# SBH_BMS.net
KiCad netlist of a schematic drawn in Altium Designer
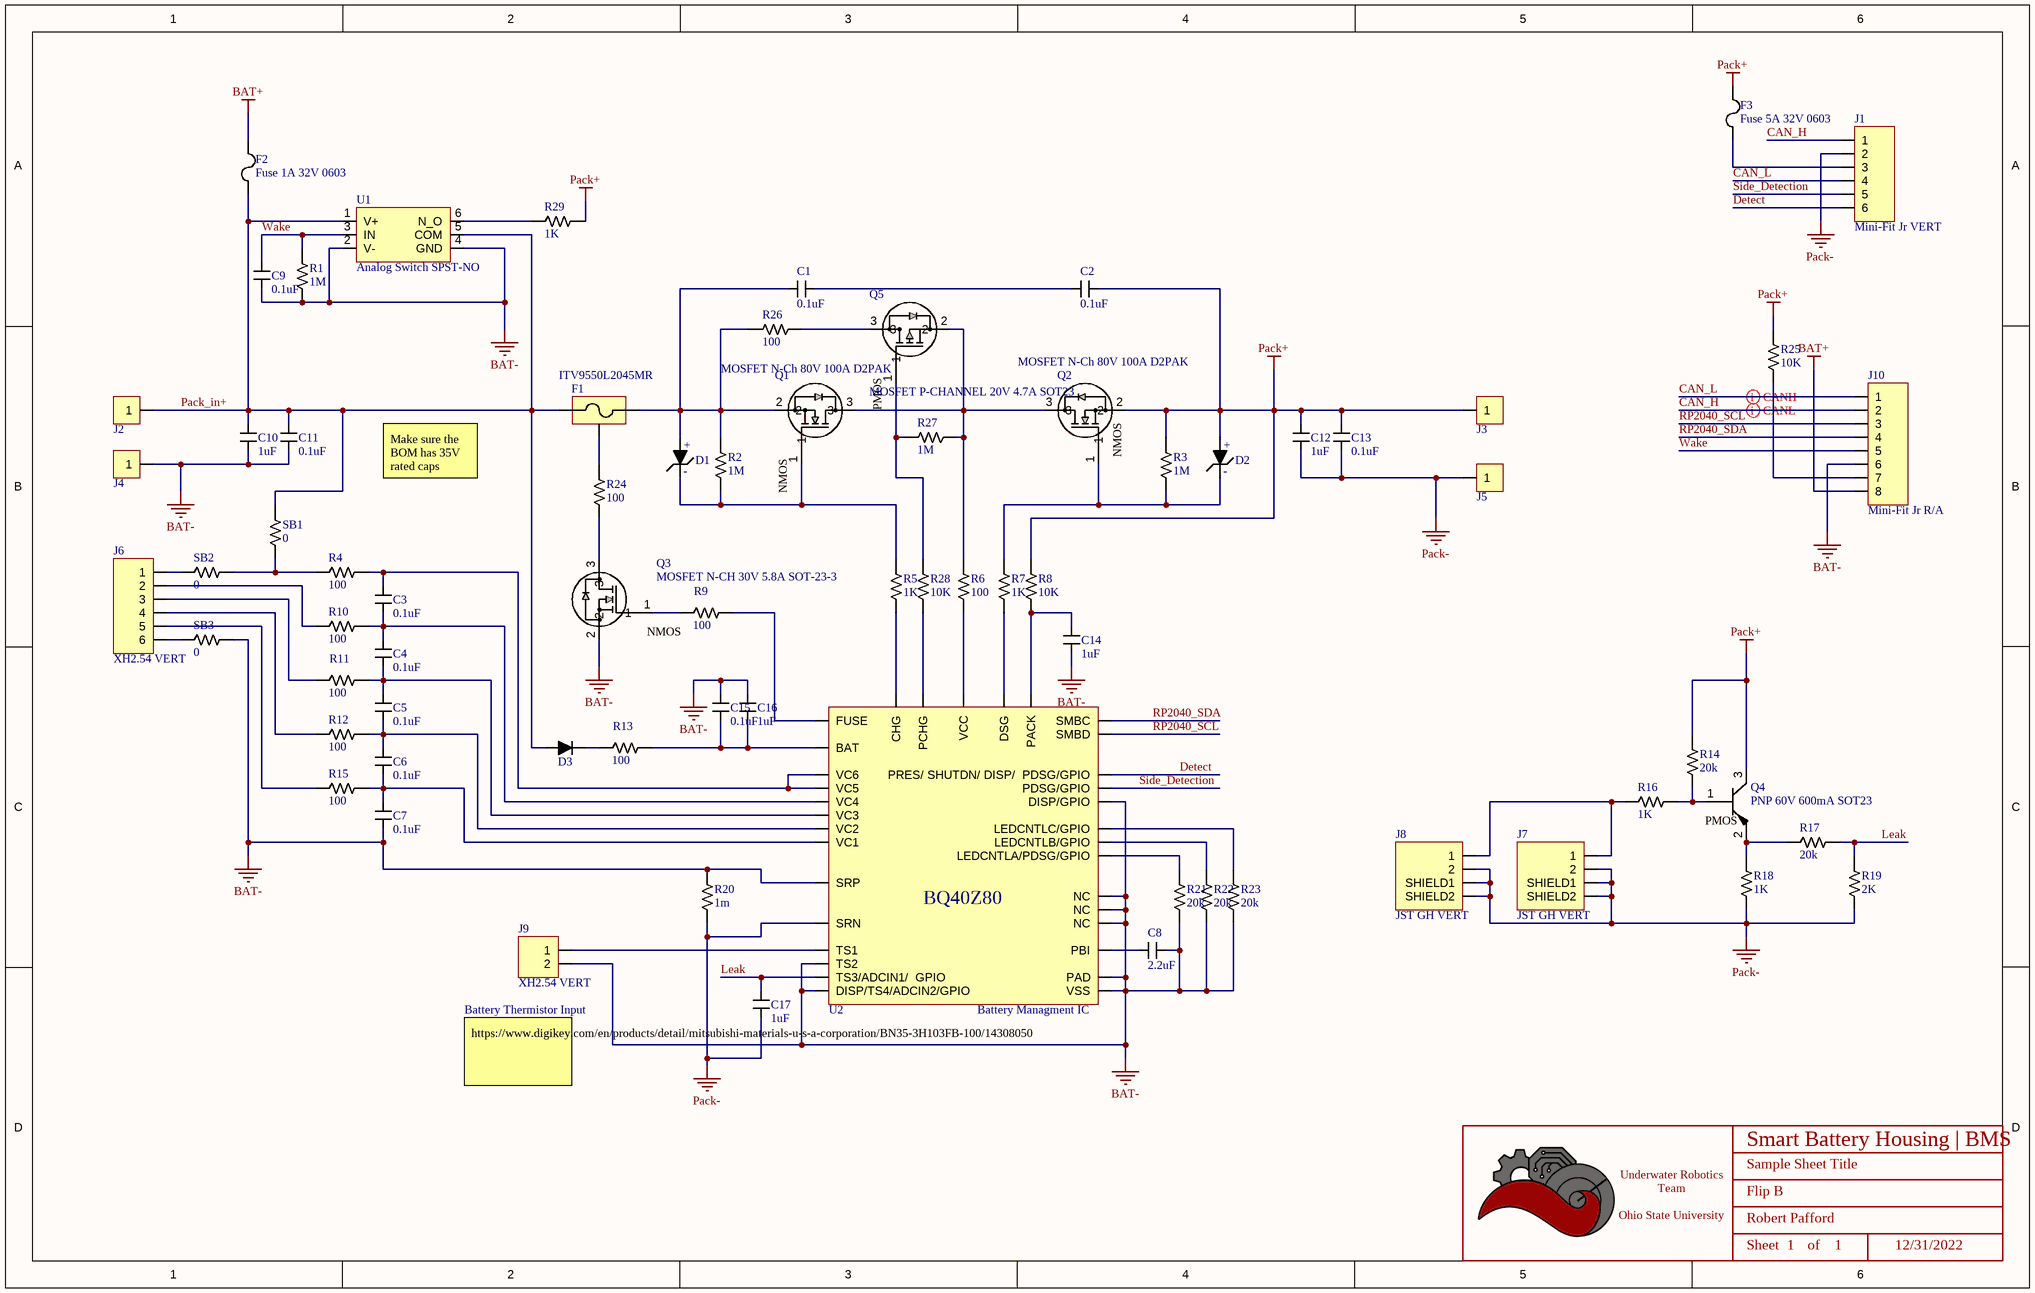
[diagram p0: SBH_BMS.SchDoc]

(export (version "E")
  (design (tool "Eeschema 10.0.6"))
  (components
    (comp (ref "*")
      (value "Title_Block")
      (footprint "LOGO")
      (description "UWRT Schematic Title Block Template\r\n\r\nCreated June 2021, Dylan Trainor")
      (libsource (lib "UWRT") (part "Title_Block"))
    )
    (comp (ref "C1")
      (value "0.1uF")
      (footprint "CAPACITOR_0402")
      (description "Cap 100nF 25V +/-10%\r\nCeramic 0402")
      (fields
        (field (name "TOLERANCE") "+/- 10%")
        (field (name "VOLTAGE") "25V")
        (field (name "MADE BY") "Robert Pafford")
      )
      (libsource (lib "Capacitors") (part "CAPACITOR_0.1uF_0402"))
    )
    (comp (ref "C2")
      (value "0.1uF")
      (footprint "CAPACITOR_0402")
      (description "Cap 100nF 25V +/-10%\r\nCeramic 0402")
      (fields
        (field (name "TOLERANCE") "+/- 10%")
        (field (name "VOLTAGE") "25V")
        (field (name "MADE BY") "Robert Pafford")
      )
      (libsource (lib "Capacitors") (part "CAPACITOR_0.1uF_0402"))
    )
    (comp (ref "C3")
      (value "0.1uF")
      (footprint "CAPACITOR_0402")
      (description "Cap 100nF 25V +/-10%\r\nCeramic 0402")
      (fields
        (field (name "TOLERANCE") "+/- 10%")
        (field (name "VOLTAGE") "25V")
        (field (name "MADE BY") "Robert Pafford")
      )
      (libsource (lib "Capacitors") (part "CAPACITOR_0.1uF_0402"))
    )
    (comp (ref "C4")
      (value "0.1uF")
      (footprint "CAPACITOR_0402")
      (description "Cap 100nF 25V +/-10%\r\nCeramic 0402")
      (fields
        (field (name "TOLERANCE") "+/- 10%")
        (field (name "VOLTAGE") "25V")
        (field (name "MADE BY") "Robert Pafford")
      )
      (libsource (lib "Capacitors") (part "CAPACITOR_0.1uF_0402"))
    )
    (comp (ref "C5")
      (value "0.1uF")
      (footprint "CAPACITOR_0402")
      (description "Cap 100nF 25V +/-10%\r\nCeramic 0402")
      (fields
        (field (name "TOLERANCE") "+/- 10%")
        (field (name "VOLTAGE") "25V")
        (field (name "MADE BY") "Robert Pafford")
      )
      (libsource (lib "Capacitors") (part "CAPACITOR_0.1uF_0402"))
    )
    (comp (ref "C6")
      (value "0.1uF")
      (footprint "CAPACITOR_0402")
      (description "Cap 100nF 25V +/-10%\r\nCeramic 0402")
      (fields
        (field (name "TOLERANCE") "+/- 10%")
        (field (name "VOLTAGE") "25V")
        (field (name "MADE BY") "Robert Pafford")
      )
      (libsource (lib "Capacitors") (part "CAPACITOR_0.1uF_0402"))
    )
    (comp (ref "C7")
      (value "0.1uF")
      (footprint "CAPACITOR_0402")
      (description "Cap 100nF 25V +/-10%\r\nCeramic 0402")
      (fields
        (field (name "TOLERANCE") "+/- 10%")
        (field (name "VOLTAGE") "25V")
        (field (name "MADE BY") "Robert Pafford")
      )
      (libsource (lib "Capacitors") (part "CAPACITOR_0.1uF_0402"))
    )
    (comp (ref "C8")
      (value "2.2uF")
      (footprint "CAPACITOR_0402")
      (description "Cap 2.2uF 35V +/-10%\r\nCeramic 0402")
      (fields
        (field (name "TOLERANCE") "+/- 10%")
        (field (name "VOLTAGE") "35V")
        (field (name "MADE BY") "Flip B")
      )
      (libsource (lib "Capacitors") (part "CAPACITOR_2.2uF_0402"))
    )
    (comp (ref "C9")
      (value "0.1uF")
      (footprint "CAPACITOR_0402")
      (description "Cap 100nF 25V +/-10%\r\nCeramic 0402")
      (fields
        (field (name "TOLERANCE") "+/- 10%")
        (field (name "VOLTAGE") "25V")
        (field (name "MADE BY") "Robert Pafford")
      )
      (libsource (lib "Capacitors") (part "CAPACITOR_0.1uF_0402"))
    )
    (comp (ref "C10")
      (value "1uF")
      (footprint "CAPACITOR_0402")
      (description "Cap 1uF 16V +/-10%\r\nCeramic 0402")
      (fields
        (field (name "TOLERANCE") "+/- 10%")
        (field (name "VOLTAGE") "16V")
        (field (name "MADE BY") "Robert Pafford")
      )
      (libsource (lib "Capacitors") (part "CAPACITOR_1uF_0402"))
    )
    (comp (ref "C11")
      (value "0.1uF")
      (footprint "CAPACITOR_0402")
      (description "Cap 100nF 25V +/-10%\r\nCeramic 0402")
      (fields
        (field (name "TOLERANCE") "+/- 10%")
        (field (name "VOLTAGE") "25V")
        (field (name "MADE BY") "Robert Pafford")
      )
      (libsource (lib "Capacitors") (part "CAPACITOR_0.1uF_0402"))
    )
    (comp (ref "C12")
      (value "1uF")
      (footprint "CAPACITOR_0402")
      (description "Cap 1uF 16V +/-10%\r\nCeramic 0402")
      (fields
        (field (name "TOLERANCE") "+/- 10%")
        (field (name "VOLTAGE") "16V")
        (field (name "MADE BY") "Robert Pafford")
      )
      (libsource (lib "Capacitors") (part "CAPACITOR_1uF_0402"))
    )
    (comp (ref "C13")
      (value "0.1uF")
      (footprint "CAPACITOR_0402")
      (description "Cap 100nF 25V +/-10%\r\nCeramic 0402")
      (fields
        (field (name "TOLERANCE") "+/- 10%")
        (field (name "VOLTAGE") "25V")
        (field (name "MADE BY") "Robert Pafford")
      )
      (libsource (lib "Capacitors") (part "CAPACITOR_0.1uF_0402"))
    )
    (comp (ref "C14")
      (value "1uF")
      (footprint "CAPACITOR_0402")
      (description "Cap 1uF 16V +/-10%\r\nCeramic 0402")
      (fields
        (field (name "TOLERANCE") "+/- 10%")
        (field (name "VOLTAGE") "16V")
        (field (name "MADE BY") "Robert Pafford")
      )
      (libsource (lib "Capacitors") (part "CAPACITOR_1uF_0402"))
    )
    (comp (ref "C15")
      (value "0.1uF")
      (footprint "CAPACITOR_0402")
      (description "Cap 100nF 25V +/-10%\r\nCeramic 0402")
      (fields
        (field (name "TOLERANCE") "+/- 10%")
        (field (name "VOLTAGE") "25V")
        (field (name "MADE BY") "Robert Pafford")
      )
      (libsource (lib "Capacitors") (part "CAPACITOR_0.1uF_0402"))
    )
    (comp (ref "C16")
      (value "1uF")
      (footprint "CAPACITOR_0402")
      (description "Cap 1uF 16V +/-10%\r\nCeramic 0402")
      (fields
        (field (name "TOLERANCE") "+/- 10%")
        (field (name "VOLTAGE") "16V")
        (field (name "MADE BY") "Robert Pafford")
      )
      (libsource (lib "Capacitors") (part "CAPACITOR_1uF_0402"))
    )
    (comp (ref "C17")
      (value "1uF")
      (footprint "CAPACITOR_0402")
      (description "Cap 1uF 16V +/-10%\r\nCeramic 0402")
      (fields
        (field (name "TOLERANCE") "+/- 10%")
        (field (name "VOLTAGE") "16V")
        (field (name "MADE BY") "Robert Pafford")
      )
      (libsource (lib "Capacitors") (part "CAPACITOR_1uF_0402"))
    )
    (comp (ref "D1")
      (value "Zener_Diode_16V_500mW")
      (footprint "SOD-123")
      (description "Zener Diode ¦ 16 V ¦ 500 mW ¦ SOD-123")
      (fields (field (name "POWER") "500mW") (field (name "MADE BY") "Flip B"))
      (libsource (lib "Diodes") (part "Zener_Diode_16V_500mW"))
    )
    (comp (ref "D2")
      (value "Zener_Diode_16V_500mW")
      (footprint "SOD-123")
      (description "Zener Diode ¦ 16 V ¦ 500 mW ¦ SOD-123")
      (fields (field (name "POWER") "500mW") (field (name "MADE BY") "Flip B"))
      (libsource (lib "Diodes") (part "Zener_Diode_16V_500mW"))
    )
    (comp (ref "D3")
      (value "MBR0520LT3G")
      (footprint "SOD-123")
      (description "Schottky Diode, 20V reverse breakdown, 500mA, Vf = 0.385V")
      (fields (field (name "MADE BY") "Flip B"))
      (libsource (lib "Diodes") (part "SCHOTTKY_20V_500mA"))
    )
    (comp (ref "F1")
      (value "ITV9550L2045MR")
      (footprint "ITV9550")
      (description "LittelFuse  ¦ 45A ¦ 5S ¦ SMD ¦ Self-Control Protector")
      (fields (field (name "CREATED BY") "Flip B"))
      (libsource (lib "Fuses") (part "ITV9550L2045MR"))
    )
    (comp (ref "F2")
      (value "Fuse 1A 32V 0603")
      (footprint "2-SMD Fuse 0603")
      (description "Pansonic ¦ 32V ¦ 1A ¦ 0603 ¦ Fast Blow")
      (fields
        (field (name "MANUFACTURER_PART_NUMBER") "ERB-RE1R00V")
        (field (name "CREATED BY") "Nathan Ayer")
      )
      (libsource (lib "Fuses") (part "ERB-RE1R00V"))
    )
    (comp (ref "F3")
      (value "Fuse 5A 32V 0603")
      (footprint "2-SMD Fuse 0603")
      (description "Pansonic ¦ 32V ¦ 5A ¦ 0603 ¦ Fast Blow")
      (fields
        (field (name "MANUFACTURER_PART_NUMBER") "ERB-RE5R00V")
        (field (name "CREATED BY") "Robert Pafford")
      )
      (libsource (lib "Fuses") (part "ERB-RE5R00V"))
    )
    (comp (ref "J1")
      (value "Mini-Fit Jr VERT")
      (footprint "CONN_MOLEX_MINIFIT JR_6 POS_VERT")
      (description "Molex Minifit Jr. 5566 \r\n6 Pos VERT Natural")
      (fields (field (name "MANUFACTURER") "Molex") (field (name "CREATED BY") "Flip B"))
      (libsource (lib "Connectors") (part "CONN_MOLEX_MINIFIT JR_6POS_VERT"))
    )
    (comp (ref "J2")
      (value "Redcube M4 Term 85A")
      (footprint "Redcube M4 Term 85A")
      (fields (field (name "CREATED BY") "Nahtan Ayer"))
      (libsource (lib "") (part "Redcube M4 Term 85A_1"))
    )
    (comp (ref "J3")
      (value "Redcube M4 Term 85A")
      (footprint "Redcube M4 Term 85A")
      (fields (field (name "CREATED BY") "Nahtan Ayer"))
      (libsource (lib "Connectors") (part "Redcube M4 Term 85A"))
    )
    (comp (ref "J4")
      (value "Redcube M4 Term 85A")
      (footprint "Redcube M4 Term 85A")
      (fields (field (name "CREATED BY") "Nahtan Ayer"))
      (libsource (lib "") (part "Redcube M4 Term 85A_1"))
    )
    (comp (ref "J5")
      (value "Redcube M4 Term 85A")
      (footprint "Redcube M4 Term 85A")
      (fields (field (name "CREATED BY") "Nahtan Ayer"))
      (libsource (lib "Connectors") (part "Redcube M4 Term 85A"))
    )
    (comp (ref "J6")
      (value "XH2.54 VERT")
      (footprint "CONN_JST_XH254_6POS_VERT")
      (description "JST XH 2.54mm Pitch 6 Pos Vertical")
      (fields (field (name "MANUFACTURER") "JST") (field (name "CREATED BY") "Flip B"))
      (libsource (lib "Connectors") (part "CONN_JST_XH254_6POS_VERT"))
    )
    (comp (ref "J7")
      (value "JST GH VERT")
      (footprint "CONN_JST_SM02B-GHS-TB(LF)(SN)")
      (description "JST GH Pitch 2 Pos Vertical")
      (fields (field (name "MANUFACTURER") "JST") (field (name "CREATED BY") "Robert P"))
      (libsource (lib "Connectors") (part "CONN_JST_GH_POS_VERT"))
    )
    (comp (ref "J8")
      (value "JST GH VERT")
      (footprint "CONN_JST_SM02B-GHS-TB(LF)(SN)")
      (description "JST GH Pitch 2 Pos Vertical")
      (fields (field (name "MANUFACTURER") "JST") (field (name "CREATED BY") "Robert P"))
      (libsource (lib "Connectors") (part "CONN_JST_GH_POS_VERT"))
    )
    (comp (ref "J9")
      (value "XH2.54 VERT")
      (footprint "CONN_JST_XH254_2POS_VERT")
      (description "JST XH 2.54mm Pitch 2 Pos Vertical")
      (fields (field (name "MANUFACTURER") "JST") (field (name "CREATED BY") "Robert P"))
      (libsource (lib "Connectors") (part "CONN_JST_XH254_2POS_VERT"))
    )
    (comp (ref "J10")
      (value "Mini-Fit Jr R/A")
      (footprint "Molex_Mili-Grid_2x4PIN_2.00MM_VERT")
      (description "Molex Mili-Grid 2.00mm pitch 8 Pos Vertical")
      (fields (field (name "MANUFACTURER") "Molex") (field (name "CREATED BY") "Flip B"))
      (libsource (lib "Connectors") (part "CONN_MOLEX_MiliGrid_8POS"))
    )
    (comp (ref "Q1")
      (value "MOSFET N-Ch 80V 100A D2PAK")
      (footprint "D2PAK")
      (description "N-Channel 80V 100A (Ta) 306W (Ta), Surface Mount D2PAK")
      (fields
        (field (name "MANUFACTURER _PART_NUMBER") "PSMN4R4-80BS,118")
        (field (name "CREATED BY") "Flip B")
      )
      (libsource (lib "Transistors") (part "PSMN4R4-80BS,118"))
    )
    (comp (ref "Q2")
      (value "MOSFET N-Ch 80V 100A D2PAK")
      (footprint "D2PAK")
      (description "N-Channel 80V 100A (Ta) 306W (Ta), Surface Mount D2PAK")
      (fields
        (field (name "MANUFACTURER _PART_NUMBER") "PSMN4R4-80BS,118")
        (field (name "CREATED BY") "Flip B")
      )
      (libsource (lib "Transistors") (part "PSMN4R4-80BS,118"))
    )
    (comp (ref "Q3")
      (value "MOSFET N-CH 30V 5.8A SOT-23-3")
      (footprint "SOT-23-3")
      (description "N-Channel 30 V 5.8A (Ta) 1.4W (Ta) Surface Mount SOT-23-3")
      (fields (field (name "MANUFACTURER _PART_NUMBER") "AO3404A") (field (name "CREATED BY") "Dylan T"))
      (libsource (lib "Transistors") (part "AO3404A"))
    )
    (comp (ref "Q4")
      (value "PNP 60V 600mA SOT23")
      (footprint "SOT-23-3")
      (description "PNP 60 V 600mA Surface Mount SOT-23")
      (fields
        (field (name "MANUFACTURER_PART_NUMBER") "MMBT2907A-7-F")
        (field (name "CREATED BY") "Robert Pafford")
      )
      (libsource (lib "Transistors") (part "MMBT2907A-7-F"))
    )
    (comp (ref "Q5")
      (value "MOSFET P-CHANNEL 20V 4.7A SOT23")
      (footprint "SOT-23-3")
      (description "P-Channel 20 V 4.7A (Tc) 1.56W (Tc) Surface Mount SOT-23")
      (fields
        (field (name "MANUFACTURER_PART_NUMBER") "TSM500P02CX")
        (field (name "CREATED BY") "Robert Pafford")
      )
      (libsource (lib "Transistors") (part "TSM500P02CX"))
    )
    (comp (ref "R1")
      (value "1M")
      (footprint "RESISTOR_0603")
      (description "RES 1M OHM 1/8W 0603")
      (fields
        (field (name "TOLERANCE") "+/- 5%")
        (field (name "VALUE  (OHMS)") "1M")
        (field (name "MADE BY") "Robert Pafford")
      )
      (libsource (lib "Resistors") (part "RESISTOR_1M_0603"))
    )
    (comp (ref "R2")
      (value "1M")
      (footprint "RESISTOR_0603")
      (description "RES 1M OHM 1/8W 0603")
      (fields
        (field (name "TOLERANCE") "+/- 5%")
        (field (name "VALUE  (OHMS)") "1M")
        (field (name "MADE BY") "Robert Pafford")
      )
      (libsource (lib "Resistors") (part "RESISTOR_1M_0603"))
    )
    (comp (ref "R3")
      (value "1M")
      (footprint "RESISTOR_0603")
      (description "RES 1M OHM 1/8W 0603")
      (fields
        (field (name "TOLERANCE") "+/- 5%")
        (field (name "VALUE  (OHMS)") "1M")
        (field (name "MADE BY") "Robert Pafford")
      )
      (libsource (lib "Resistors") (part "RESISTOR_1M_0603"))
    )
    (comp (ref "R4")
      (value "100 Ohm 5% 1/16W")
      (footprint "RESISTOR_0402")
      (description "RES 100 OHM 5% 1/16W 0402")
      (fields
        (field (name "TOLERANCE") "+/- 5%")
        (field (name "VALUE  (OHMS)") "100")
        (field (name "MADE BY") "Flip B")
      )
      (libsource (lib "Resistors") (part "RESISTOR_100_0402"))
    )
    (comp (ref "R5")
      (value "1k Ohm 1% 1/16W")
      (footprint "RESISTOR_0402")
      (description "RES 1k OHM 1% 1/16W 0402")
      (fields
        (field (name "TOLERANCE") "+/- 1%")
        (field (name "VALUE  (OHMS)") "1K")
        (field (name "MADE BY") "Robert Pafford")
      )
      (libsource (lib "Resistors") (part "RESISTOR_1K_0402"))
    )
    (comp (ref "R6")
      (value "100 Ohm 5% 1/16W")
      (footprint "RESISTOR_0402")
      (description "RES 100 OHM 5% 1/16W 0402")
      (fields
        (field (name "TOLERANCE") "+/- 5%")
        (field (name "VALUE  (OHMS)") "100")
        (field (name "MADE BY") "Flip B")
      )
      (libsource (lib "Resistors") (part "RESISTOR_100_0402"))
    )
    (comp (ref "R7")
      (value "1k Ohm 1% 1/16W")
      (footprint "RESISTOR_0402")
      (description "RES 1k OHM 1% 1/16W 0402")
      (fields
        (field (name "TOLERANCE") "+/- 1%")
        (field (name "VALUE  (OHMS)") "1K")
        (field (name "MADE BY") "Robert Pafford")
      )
      (libsource (lib "Resistors") (part "RESISTOR_1K_0402"))
    )
    (comp (ref "R8")
      (value "10k Ohm 1% 1/16W")
      (footprint "RESISTOR_0402")
      (description "RES 10k OHM 1% 1/16W 0402")
      (fields
        (field (name "TOLERANCE") "+/- 1%")
        (field (name "VALUE  (OHMS)") "10K")
        (field (name "MADE BY") "Robert Pafford")
      )
      (libsource (lib "Resistors") (part "RESISTOR_10K_0402"))
    )
    (comp (ref "R9")
      (value "100 Ohm 5% 1/16W")
      (footprint "RESISTOR_0402")
      (description "RES 100 OHM 5% 1/16W 0402")
      (fields
        (field (name "TOLERANCE") "+/- 5%")
        (field (name "VALUE  (OHMS)") "100")
        (field (name "MADE BY") "Flip B")
      )
      (libsource (lib "Resistors") (part "RESISTOR_100_0402"))
    )
    (comp (ref "R10")
      (value "100 Ohm 5% 1/16W")
      (footprint "RESISTOR_0402")
      (description "RES 100 OHM 5% 1/16W 0402")
      (fields
        (field (name "TOLERANCE") "+/- 5%")
        (field (name "VALUE  (OHMS)") "100")
        (field (name "MADE BY") "Flip B")
      )
      (libsource (lib "Resistors") (part "RESISTOR_100_0402"))
    )
    (comp (ref "R11")
      (value "100 Ohm 5% 1/16W")
      (footprint "RESISTOR_0402")
      (description "RES 100 OHM 5% 1/16W 0402")
      (fields
        (field (name "TOLERANCE") "+/- 5%")
        (field (name "VALUE  (OHMS)") "100")
        (field (name "MADE BY") "Flip B")
      )
      (libsource (lib "Resistors") (part "RESISTOR_100_0402"))
    )
    (comp (ref "R12")
      (value "100 Ohm 5% 1/16W")
      (footprint "RESISTOR_0402")
      (description "RES 100 OHM 5% 1/16W 0402")
      (fields
        (field (name "TOLERANCE") "+/- 5%")
        (field (name "VALUE  (OHMS)") "100")
        (field (name "MADE BY") "Flip B")
      )
      (libsource (lib "Resistors") (part "RESISTOR_100_0402"))
    )
    (comp (ref "R13")
      (value "100 Ohm 5% 1/16W")
      (footprint "RESISTOR_0402")
      (description "RES 100 OHM 5% 1/16W 0402")
      (fields
        (field (name "TOLERANCE") "+/- 5%")
        (field (name "VALUE  (OHMS)") "100")
        (field (name "MADE BY") "Flip B")
      )
      (libsource (lib "Resistors") (part "RESISTOR_100_0402"))
    )
    (comp (ref "R14")
      (value "20k Ohm 1% 1/16W")
      (footprint "RESISTOR_0402")
      (description "RES 20k OHM 1% 1/16W 0402")
      (fields
        (field (name "TOLERANCE") "+/- 1%")
        (field (name "VALUE  (OHMS)") "20k")
        (field (name "MADE BY") "Flip B")
      )
      (libsource (lib "Resistors") (part "RESISTOR_20K_0402"))
    )
    (comp (ref "R15")
      (value "100 Ohm 5% 1/16W")
      (footprint "RESISTOR_0402")
      (description "RES 100 OHM 5% 1/16W 0402")
      (fields
        (field (name "TOLERANCE") "+/- 5%")
        (field (name "VALUE  (OHMS)") "100")
        (field (name "MADE BY") "Flip B")
      )
      (libsource (lib "Resistors") (part "RESISTOR_100_0402"))
    )
    (comp (ref "R16")
      (value "1k Ohm 1% 1/16W")
      (footprint "RESISTOR_0402")
      (description "RES 1k OHM 1% 1/16W 0402")
      (fields
        (field (name "TOLERANCE") "+/- 1%")
        (field (name "VALUE  (OHMS)") "1K")
        (field (name "MADE BY") "Robert Pafford")
      )
      (libsource (lib "Resistors") (part "RESISTOR_1K_0402"))
    )
    (comp (ref "R17")
      (value "20k Ohm 1% 1/16W")
      (footprint "RESISTOR_0402")
      (description "RES 20k OHM 1% 1/16W 0402")
      (fields
        (field (name "TOLERANCE") "+/- 1%")
        (field (name "VALUE  (OHMS)") "20k")
        (field (name "MADE BY") "Flip B")
      )
      (libsource (lib "Resistors") (part "RESISTOR_20K_0402"))
    )
    (comp (ref "R18")
      (value "1k Ohm 1% 1/16W")
      (footprint "RESISTOR_0402")
      (description "RES 1k OHM 1% 1/16W 0402")
      (fields
        (field (name "TOLERANCE") "+/- 1%")
        (field (name "VALUE  (OHMS)") "1K")
        (field (name "MADE BY") "Robert Pafford")
      )
      (libsource (lib "Resistors") (part "RESISTOR_1K_0402"))
    )
    (comp (ref "R19")
      (value "2k Ohm 1% 1/16W")
      (footprint "RESISTOR_0402")
      (description "RES 2k OHM 1% 1/16W 0402")
      (fields
        (field (name "TOLERANCE") "+/- 1%")
        (field (name "VALUE  (OHMS)") "2K")
        (field (name "MADE BY") "Flip B")
      )
      (libsource (lib "Resistors") (part "RESISTOR_2K_0402"))
    )
    (comp (ref "R20")
      (value "1m Ohm 5% 8W")
      (footprint "RES_CSS2H-3920")
      (description "RES 1m OHM 1% 8W Current Sense")
      (fields
        (field (name "TOLERANCE") "+/- 1%")
        (field (name "VALUE  (OHMS)") "1m")
        (field (name "MADE BY") "Flip B")
      )
      (libsource (lib "Resistors") (part "RESISTOR_1m_CS"))
    )
    (comp (ref "R21")
      (value "20k Ohm 1% 1/16W")
      (footprint "RESISTOR_0402")
      (description "RES 20k OHM 1% 1/16W 0402")
      (fields
        (field (name "TOLERANCE") "+/- 1%")
        (field (name "VALUE  (OHMS)") "20k")
        (field (name "MADE BY") "Flip B")
      )
      (libsource (lib "Resistors") (part "RESISTOR_20K_0402"))
    )
    (comp (ref "R22")
      (value "20k Ohm 1% 1/16W")
      (footprint "RESISTOR_0402")
      (description "RES 20k OHM 1% 1/16W 0402")
      (fields
        (field (name "TOLERANCE") "+/- 1%")
        (field (name "VALUE  (OHMS)") "20k")
        (field (name "MADE BY") "Flip B")
      )
      (libsource (lib "Resistors") (part "RESISTOR_20K_0402"))
    )
    (comp (ref "R23")
      (value "20k Ohm 1% 1/16W")
      (footprint "RESISTOR_0402")
      (description "RES 20k OHM 1% 1/16W 0402")
      (fields
        (field (name "TOLERANCE") "+/- 1%")
        (field (name "VALUE  (OHMS)") "20k")
        (field (name "MADE BY") "Flip B")
      )
      (libsource (lib "Resistors") (part "RESISTOR_20K_0402"))
    )
    (comp (ref "R24")
      (value "100 Ohm 5% 1/16W")
      (footprint "RESISTOR_0402")
      (description "RES 100 OHM 5% 1/16W 0402")
      (fields
        (field (name "TOLERANCE") "+/- 5%")
        (field (name "VALUE  (OHMS)") "100")
        (field (name "MADE BY") "Flip B")
      )
      (libsource (lib "Resistors") (part "RESISTOR_100_0402"))
    )
    (comp (ref "R25")
      (value "10k Ohm 5% 1/10W")
      (footprint "RESISTOR_0603")
      (description "RES 10k OHM 5% 1/10W 0603")
      (fields
        (field (name "TOLERANCE") "+/- 5%")
        (field (name "VALUE  (OHMS)") "10K")
        (field (name "MADE BY") "Robert Pafford")
      )
      (libsource (lib "Resistors") (part "RESISTOR_10K_0603"))
    )
    (comp (ref "R26")
      (value "100 Ohm 5% 1/16W")
      (footprint "RESISTOR_0402")
      (description "RES 100 OHM 5% 1/16W 0402")
      (fields
        (field (name "TOLERANCE") "+/- 5%")
        (field (name "VALUE  (OHMS)") "100")
        (field (name "MADE BY") "Flip B")
      )
      (libsource (lib "Resistors") (part "RESISTOR_100_0402"))
    )
    (comp (ref "R27")
      (value "1M")
      (footprint "RESISTOR_0603")
      (description "RES 1M OHM 1/8W 0603")
      (fields
        (field (name "TOLERANCE") "+/- 5%")
        (field (name "VALUE  (OHMS)") "1M")
        (field (name "MADE BY") "Robert Pafford")
      )
      (libsource (lib "Resistors") (part "RESISTOR_1M_0603"))
    )
    (comp (ref "R28")
      (value "10k Ohm 1% 1/16W")
      (footprint "RESISTOR_0402")
      (description "RES 10k OHM 1% 1/16W 0402")
      (fields
        (field (name "TOLERANCE") "+/- 1%")
        (field (name "VALUE  (OHMS)") "10K")
        (field (name "MADE BY") "Robert Pafford")
      )
      (libsource (lib "Resistors") (part "RESISTOR_10K_0402"))
    )
    (comp (ref "R29")
      (value "1k Ohm 5% 1/8W")
      (footprint "RESISTOR_0603")
      (description "RES 1k OHM 5% 1/8W 0603")
      (fields
        (field (name "TOLERANCE") "+/- 5%")
        (field (name "VALUE  (OHMS)") "1K")
        (field (name "MADE BY") "Robert Pafford")
      )
      (libsource (lib "Resistors") (part "RESISTOR_1K_0603"))
    )
    (comp (ref "SB1")
      (value "0 Ohm Jumper No Fit")
      (footprint "RESISTOR_0603")
      (description "0 Ohm Jumper No Fit for Solder Bridge")
      (fields (field (name "VALUE  (OHMS)") "0") (field (name "MADE BY") "Robert Pafford"))
      (libsource (lib "Resistors") (part "JUMPER_0_0603"))
    )
    (comp (ref "SB2")
      (value "0 Ohm Jumper No Fit")
      (footprint "RESISTOR_0603")
      (description "0 Ohm Jumper No Fit for Solder Bridge")
      (fields (field (name "VALUE  (OHMS)") "0") (field (name "MADE BY") "Robert Pafford"))
      (libsource (lib "Resistors") (part "JUMPER_0_0603"))
    )
    (comp (ref "SB3")
      (value "0 Ohm Jumper No Fit")
      (footprint "RESISTOR_0603")
      (description "0 Ohm Jumper No Fit for Solder Bridge")
      (fields (field (name "VALUE  (OHMS)") "0") (field (name "MADE BY") "Robert Pafford"))
      (libsource (lib "Resistors") (part "JUMPER_0_0603"))
    )
    (comp (ref "U1")
      (value "Analog Switch SPST-NO")
      (footprint "TSOT-23_S6")
      (description "Analog Switch SPST Normally Open")
      (fields
        (field (name "MF") "Analog Devices")
        (field (name "VOLTAGE") "9-36V")
        (field (name "CREATED BY") "Flip B")
      )
      (libsource (lib "Integrated Circuits") (part "MAX4520EUT+T"))
    )
    (comp (ref "U2")
      (value "Battery Managment IC")
      (footprint "VQFN-32")
      (description "Multifuntion Li-ion/ Lipo Battery Pack Managment IC")
      (fields
        (field (name "MANUFACTURER") "Texas Instruments")
        (field (name "PARTNUMBER") "BQ40Z80RSMT")
        (field (name "CREATED BY") "Flip B")
      )
      (libsource (lib "Integrated Circuits") (part "BQ40Z80RSMT"))
    )
  )
  (nets
    (net (code "1") (name "/CAN_H") (class "Default")
      (node (ref "J1") (pin "1") (pinfunction "1_1") (pintype "passive"))
      (node (ref "J10") (pin "2") (pinfunction "2_2") (pintype "passive"))
    )
    (net (code "2") (name "/CAN_L") (class "Default")
      (node (ref "J1") (pin "4") (pinfunction "4_4") (pintype "passive"))
      (node (ref "J10") (pin "1") (pinfunction "1_1") (pintype "passive"))
    )
    (net (code "3") (name "/Detect") (class "Default")
      (node (ref "J1") (pin "6") (pinfunction "6_6") (pintype "passive"))
      (node (ref "U2") (pin "17") (pinfunction "PRES/_SHUTDN/_DISP/__PDSG/GPIO_17") (pintype "passive"))
    )
    (net (code "4") (name "/Leak") (class "Default")
      (node (ref "C17") (pin "1") (pinfunction "1_1") (pintype "passive"))
      (node (ref "R17") (pin "1") (pinfunction "1_1") (pintype "passive"))
      (node (ref "R19") (pin "1") (pinfunction "1_1") (pintype "passive"))
      (node (ref "U2") (pin "12") (pinfunction "TS3/ADCIN1/__GPIO_12") (pintype "passive"))
    )
    (net (code "5") (name "/Pack_in+") (class "Default")
      (node (ref "C10") (pin "1") (pinfunction "1_1") (pintype "passive"))
      (node (ref "C11") (pin "1") (pinfunction "1_1") (pintype "passive"))
      (node (ref "D3") (pin "1") (pinfunction "1_1") (pintype "passive"))
      (node (ref "F1") (pin "2") (pinfunction "2_2") (pintype "passive"))
      (node (ref "F2") (pin "1") (pinfunction "1_1") (pintype "passive"))
      (node (ref "J2") (pin "1") (pinfunction "1_1") (pintype "passive"))
      (node (ref "SB1") (pin "1") (pinfunction "1_1") (pintype "passive"))
      (node (ref "U1") (pin "1") (pinfunction "V+_1") (pintype "passive"))
      (node (ref "U1") (pin "5") (pinfunction "COM_5") (pintype "passive"))
    )
    (net (code "6") (name "/RP2040_SCL") (class "Default")
      (node (ref "J10") (pin "3") (pinfunction "3_3") (pintype "passive"))
      (node (ref "U2") (pin "18") (pinfunction "SMBD_18") (pintype "passive"))
    )
    (net (code "7") (name "/RP2040_SDA") (class "Default")
      (node (ref "J10") (pin "4") (pinfunction "4_4") (pintype "passive"))
      (node (ref "U2") (pin "19") (pinfunction "SMBC_19") (pintype "passive"))
    )
    (net (code "8") (name "/Side_Detection") (class "Default")
      (node (ref "J1") (pin "5") (pinfunction "5_5") (pintype "passive"))
      (node (ref "U2") (pin "16") (pinfunction "PDSG/GPIO_16") (pintype "passive"))
    )
    (net (code "9") (name "/Wake") (class "Default")
      (node (ref "C9") (pin "1") (pinfunction "1_1") (pintype "passive"))
      (node (ref "J10") (pin "5") (pinfunction "5_5") (pintype "passive"))
      (node (ref "R1") (pin "1") (pinfunction "1_1") (pintype "passive"))
      (node (ref "U1") (pin "3") (pinfunction "IN_3") (pintype "passive"))
    )
    (net (code "10") (name "BAT+") (class "Default")
      (node (ref "F2") (pin "2") (pinfunction "2_2") (pintype "passive"))
      (node (ref "J10") (pin "8") (pinfunction "8_8") (pintype "passive"))
    )
    (net (code "11") (name "BAT-") (class "Default")
      (node (ref "C10") (pin "2") (pinfunction "2_2") (pintype "passive"))
      (node (ref "C11") (pin "2") (pinfunction "2_2") (pintype "passive"))
      (node (ref "C14") (pin "2") (pinfunction "2_2") (pintype "passive"))
      (node (ref "C15") (pin "1") (pinfunction "1_1") (pintype "passive"))
      (node (ref "C16") (pin "1") (pinfunction "1_1") (pintype "passive"))
      (node (ref "C7") (pin "2") (pinfunction "2_2") (pintype "passive"))
      (node (ref "C8") (pin "1") (pinfunction "1_1") (pintype "passive"))
      (node (ref "C9") (pin "2") (pinfunction "2_2") (pintype "passive"))
      (node (ref "J10") (pin "6") (pinfunction "6_6") (pintype "passive"))
      (node (ref "J4") (pin "1") (pinfunction "1_1") (pintype "passive"))
      (node (ref "J9") (pin "2") (pinfunction "2_2") (pintype "passive"))
      (node (ref "Q3") (pin "2") (pinfunction "2_2") (pintype "passive"))
      (node (ref "R1") (pin "2") (pinfunction "2_2") (pintype "passive"))
      (node (ref "R20") (pin "1") (pinfunction "1_1") (pintype "passive"))
      (node (ref "R21") (pin "2") (pinfunction "2_2") (pintype "passive"))
      (node (ref "R22") (pin "2") (pinfunction "2_2") (pintype "passive"))
      (node (ref "R23") (pin "2") (pinfunction "2_2") (pintype "passive"))
      (node (ref "SB3") (pin "1") (pinfunction "1_1") (pintype "passive"))
      (node (ref "U1") (pin "2") (pinfunction "V-_2") (pintype "power_in"))
      (node (ref "U1") (pin "4") (pinfunction "GND_4") (pintype "passive"))
      (node (ref "U2") (pin "11") (pinfunction "TS2_11") (pintype "passive"))
      (node (ref "U2") (pin "13") (pinfunction "DISP/TS4/ADCIN2/GPIO_13") (pintype "passive"))
      (node (ref "U2") (pin "14") (pinfunction "NC_14") (pintype "passive"))
      (node (ref "U2") (pin "15") (pinfunction "DISP/GPIO_15") (pintype "passive"))
      (node (ref "U2") (pin "27") (pinfunction "NC_27") (pintype "passive"))
      (node (ref "U2") (pin "33") (pinfunction "PAD_33") (pintype "passive"))
      (node (ref "U2") (pin "7") (pinfunction "NC_7") (pintype "passive"))
      (node (ref "U2") (pin "8") (pinfunction "SRP_8") (pintype "passive"))
      (node (ref "U2") (pin "9") (pinfunction "VSS_9") (pintype "passive"))
    )
    (net (code "12") (name "Net-(C1-Pad1)") (class "Default")
      (node (ref "C1") (pin "1") (pinfunction "1_1") (pintype "passive"))
      (node (ref "C2") (pin "2") (pinfunction "2_2") (pintype "passive"))
    )
    (net (code "13") (name "Net-(C1-Pad2)") (class "Default")
      (node (ref "C1") (pin "2") (pinfunction "2_2") (pintype "passive"))
      (node (ref "D1") (pin "1") (pinfunction "1_1") (pintype "passive"))
      (node (ref "F1") (pin "1") (pinfunction "1_1") (pintype "passive"))
      (node (ref "Q1") (pin "2") (pinfunction "2_2") (pintype "passive"))
      (node (ref "R2") (pin "1") (pinfunction "1_1") (pintype "passive"))
      (node (ref "R26") (pin "1") (pinfunction "1_1") (pintype "passive"))
    )
    (net (code "14") (name "Net-(D1-Pad2)") (class "Default")
      (node (ref "D1") (pin "2") (pinfunction "2_2") (pintype "passive"))
      (node (ref "Q1") (pin "1") (pinfunction "1_1") (pintype "passive"))
      (node (ref "R2") (pin "2") (pinfunction "2_2") (pintype "passive"))
      (node (ref "R5") (pin "1") (pinfunction "1_1") (pintype "passive"))
    )
    (net (code "15") (name "Net-(D2-Pad2)") (class "Default")
      (node (ref "D2") (pin "2") (pinfunction "2_2") (pintype "passive"))
      (node (ref "Q2") (pin "1") (pinfunction "1_1") (pintype "passive"))
      (node (ref "R3") (pin "2") (pinfunction "2_2") (pintype "passive"))
      (node (ref "R7") (pin "1") (pinfunction "1_1") (pintype "passive"))
    )
    (net (code "16") (name "Net-(D3-Pad2)") (class "Default")
      (node (ref "D3") (pin "2") (pinfunction "2_2") (pintype "passive"))
      (node (ref "R13") (pin "2") (pinfunction "2_2") (pintype "passive"))
    )
    (net (code "17") (name "Net-(F1-Pad3)") (class "Default")
      (node (ref "F1") (pin "3") (pinfunction "3_3") (pintype "passive"))
      (node (ref "R24") (pin "1") (pinfunction "1_1") (pintype "passive"))
    )
    (net (code "18") (name "Net-(F3-Pad1)") (class "Default")
      (node (ref "F3") (pin "1") (pinfunction "1_1") (pintype "passive"))
      (node (ref "J1") (pin "3") (pinfunction "3_3") (pintype "passive"))
    )
    (net (code "19") (name "Net-(J6-Pad1)") (class "Default")
      (node (ref "J6") (pin "1") (pinfunction "1_1") (pintype "passive"))
      (node (ref "SB2") (pin "2") (pinfunction "2_2") (pintype "passive"))
    )
    (net (code "20") (name "Net-(J6-Pad2)") (class "Default")
      (node (ref "J6") (pin "2") (pinfunction "2_2") (pintype "passive"))
      (node (ref "R10") (pin "2") (pinfunction "2_2") (pintype "passive"))
    )
    (net (code "21") (name "Net-(J6-Pad3)") (class "Default")
      (node (ref "J6") (pin "3") (pinfunction "3_3") (pintype "passive"))
      (node (ref "R11") (pin "2") (pinfunction "2_2") (pintype "passive"))
    )
    (net (code "22") (name "Net-(J6-Pad4)") (class "Default")
      (node (ref "J6") (pin "4") (pinfunction "4_4") (pintype "passive"))
      (node (ref "R12") (pin "2") (pinfunction "2_2") (pintype "passive"))
    )
    (net (code "23") (name "Net-(J6-Pad5)") (class "Default")
      (node (ref "J6") (pin "5") (pinfunction "5_5") (pintype "passive"))
      (node (ref "R15") (pin "2") (pinfunction "2_2") (pintype "passive"))
    )
    (net (code "24") (name "Net-(J6-Pad6)") (class "Default")
      (node (ref "J6") (pin "6") (pinfunction "6_6") (pintype "passive"))
      (node (ref "SB3") (pin "2") (pinfunction "2_2") (pintype "passive"))
    )
    (net (code "25") (name "Net-(J7-Pad1)") (class "Default")
      (node (ref "J7") (pin "1") (pinfunction "1_1") (pintype "passive"))
      (node (ref "J8") (pin "1") (pinfunction "1_1") (pintype "passive"))
      (node (ref "R16") (pin "2") (pinfunction "2_2") (pintype "passive"))
    )
    (net (code "26") (name "Net-(J10-Pad7)") (class "Default")
      (node (ref "J10") (pin "7") (pinfunction "7_7") (pintype "passive"))
      (node (ref "R25") (pin "2") (pinfunction "2_2") (pintype "passive"))
    )
    (net (code "27") (name "Net-(Q1-Pad3)") (class "Default")
      (node (ref "Q1") (pin "3") (pinfunction "3_3") (pintype "passive"))
      (node (ref "Q2") (pin "3") (pinfunction "3_3") (pintype "passive"))
      (node (ref "Q5") (pin "2") (pinfunction "2_2") (pintype "passive"))
      (node (ref "R27") (pin "2") (pinfunction "2_2") (pintype "passive"))
      (node (ref "R6") (pin "1") (pinfunction "1_1") (pintype "passive"))
    )
    (net (code "28") (name "Net-(Q3-Pad1)") (class "Default")
      (node (ref "Q3") (pin "1") (pinfunction "1_1") (pintype "passive"))
      (node (ref "R9") (pin "2") (pinfunction "2_2") (pintype "passive"))
    )
    (net (code "29") (name "Net-(Q3-Pad3)") (class "Default")
      (node (ref "Q3") (pin "3") (pinfunction "3_3") (pintype "passive"))
      (node (ref "R24") (pin "2") (pinfunction "2_2") (pintype "passive"))
    )
    (net (code "30") (name "Net-(Q4-Pad1)") (class "Default")
      (node (ref "Q4") (pin "1") (pinfunction "1_1") (pintype "passive"))
      (node (ref "R14") (pin "2") (pinfunction "2_2") (pintype "passive"))
      (node (ref "R16") (pin "1") (pinfunction "1_1") (pintype "passive"))
    )
    (net (code "31") (name "Net-(Q4-Pad2)") (class "Default")
      (node (ref "Q4") (pin "2") (pinfunction "2_2") (pintype "passive"))
      (node (ref "R17") (pin "2") (pinfunction "2_2") (pintype "passive"))
      (node (ref "R18") (pin "1") (pinfunction "1_1") (pintype "passive"))
    )
    (net (code "32") (name "Net-(Q5-Pad1)") (class "Default")
      (node (ref "Q5") (pin "1") (pinfunction "1_1") (pintype "passive"))
      (node (ref "R27") (pin "1") (pinfunction "1_1") (pintype "passive"))
      (node (ref "R28") (pin "1") (pinfunction "1_1") (pintype "passive"))
    )
    (net (code "33") (name "Net-(Q5-Pad3)") (class "Default")
      (node (ref "Q5") (pin "3") (pinfunction "3_3") (pintype "passive"))
      (node (ref "R26") (pin "2") (pinfunction "2_2") (pintype "passive"))
    )
    (net (code "34") (name "Net-(R4-Pad2)") (class "Default")
      (node (ref "R4") (pin "2") (pinfunction "2_2") (pintype "passive"))
      (node (ref "SB1") (pin "2") (pinfunction "2_2") (pintype "passive"))
      (node (ref "SB2") (pin "1") (pinfunction "1_1") (pintype "passive"))
    )
    (net (code "35") (name "Net-(U1-N_O)") (class "Default")
      (node (ref "R29") (pin "2") (pinfunction "2_2") (pintype "passive"))
      (node (ref "U1") (pin "6") (pinfunction "N_O_6") (pintype "passive"))
    )
    (net (code "36") (name "Net-(U2-BAT)") (class "Default")
      (node (ref "C15") (pin "2") (pinfunction "2_2") (pintype "passive"))
      (node (ref "C16") (pin "2") (pinfunction "2_2") (pintype "passive"))
      (node (ref "R13") (pin "1") (pinfunction "1_1") (pintype "passive"))
      (node (ref "U2") (pin "30") (pinfunction "BAT_30") (pintype "passive"))
    )
    (net (code "37") (name "Net-(U2-CHG)") (class "Default")
      (node (ref "R5") (pin "2") (pinfunction "2_2") (pintype "passive"))
      (node (ref "U2") (pin "29") (pinfunction "CHG_29") (pintype "passive"))
    )
    (net (code "38") (name "Net-(U2-DSG)") (class "Default")
      (node (ref "R7") (pin "2") (pinfunction "2_2") (pintype "passive"))
      (node (ref "U2") (pin "26") (pinfunction "DSG_26") (pintype "passive"))
    )
    (net (code "39") (name "Net-(U2-FUSE)") (class "Default")
      (node (ref "R9") (pin "1") (pinfunction "1_1") (pintype "passive"))
      (node (ref "U2") (pin "23") (pinfunction "FUSE_23") (pintype "passive"))
    )
    (net (code "40") (name "Net-(U2-LEDCNTLA{slash}PDSG{slash}GPIO)") (class "Default")
      (node (ref "R21") (pin "1") (pinfunction "1_1") (pintype "passive"))
      (node (ref "U2") (pin "20") (pinfunction "LEDCNTLA/PDSG/GPIO_20") (pintype "passive"))
    )
    (net (code "41") (name "Net-(U2-LEDCNTLB{slash}GPIO)") (class "Default")
      (node (ref "R22") (pin "1") (pinfunction "1_1") (pintype "passive"))
      (node (ref "U2") (pin "21") (pinfunction "LEDCNTLB/GPIO_21") (pintype "passive"))
    )
    (net (code "42") (name "Net-(U2-LEDCNTLC{slash}GPIO)") (class "Default")
      (node (ref "R23") (pin "1") (pinfunction "1_1") (pintype "passive"))
      (node (ref "U2") (pin "22") (pinfunction "LEDCNTLC/GPIO_22") (pintype "passive"))
    )
    (net (code "43") (name "Net-(U2-PACK)") (class "Default")
      (node (ref "C14") (pin "1") (pinfunction "1_1") (pintype "passive"))
      (node (ref "R8") (pin "2") (pinfunction "2_2") (pintype "passive"))
      (node (ref "U2") (pin "25") (pinfunction "PACK_25") (pintype "passive"))
    )
    (net (code "44") (name "Net-(U2-PBI)") (class "Default")
      (node (ref "C8") (pin "2") (pinfunction "2_2") (pintype "passive"))
      (node (ref "U2") (pin "31") (pinfunction "PBI_31") (pintype "passive"))
    )
    (net (code "45") (name "Net-(U2-PCHG)") (class "Default")
      (node (ref "R28") (pin "2") (pinfunction "2_2") (pintype "passive"))
      (node (ref "U2") (pin "28") (pinfunction "PCHG_28") (pintype "passive"))
    )
    (net (code "46") (name "Net-(U2-TS1)") (class "Default")
      (node (ref "J9") (pin "1") (pinfunction "1_1") (pintype "passive"))
      (node (ref "U2") (pin "10") (pinfunction "TS1_10") (pintype "passive"))
    )
    (net (code "47") (name "Net-(U2-VC1)") (class "Default")
      (node (ref "C6") (pin "2") (pinfunction "2_2") (pintype "passive"))
      (node (ref "C7") (pin "1") (pinfunction "1_1") (pintype "passive"))
      (node (ref "R15") (pin "1") (pinfunction "1_1") (pintype "passive"))
      (node (ref "U2") (pin "5") (pinfunction "VC1_5") (pintype "passive"))
    )
    (net (code "48") (name "Net-(U2-VC2)") (class "Default")
      (node (ref "C5") (pin "2") (pinfunction "2_2") (pintype "passive"))
      (node (ref "C6") (pin "1") (pinfunction "1_1") (pintype "passive"))
      (node (ref "R12") (pin "1") (pinfunction "1_1") (pintype "passive"))
      (node (ref "U2") (pin "4") (pinfunction "VC2_4") (pintype "passive"))
    )
    (net (code "49") (name "Net-(U2-VC3)") (class "Default")
      (node (ref "C4") (pin "2") (pinfunction "2_2") (pintype "passive"))
      (node (ref "C5") (pin "1") (pinfunction "1_1") (pintype "passive"))
      (node (ref "R11") (pin "1") (pinfunction "1_1") (pintype "passive"))
      (node (ref "U2") (pin "3") (pinfunction "VC3_3") (pintype "passive"))
    )
    (net (code "50") (name "Net-(U2-VC4)") (class "Default")
      (node (ref "C3") (pin "2") (pinfunction "2_2") (pintype "passive"))
      (node (ref "C4") (pin "1") (pinfunction "1_1") (pintype "passive"))
      (node (ref "R10") (pin "1") (pinfunction "1_1") (pintype "passive"))
      (node (ref "U2") (pin "2") (pinfunction "VC4_2") (pintype "passive"))
    )
    (net (code "51") (name "Net-(U2-VC5)") (class "Default")
      (node (ref "C3") (pin "1") (pinfunction "1_1") (pintype "passive"))
      (node (ref "R4") (pin "1") (pinfunction "1_1") (pintype "passive"))
      (node (ref "U2") (pin "1") (pinfunction "VC5_1") (pintype "passive"))
      (node (ref "U2") (pin "32") (pinfunction "VC6_32") (pintype "passive"))
    )
    (net (code "52") (name "Net-(U2-VCC)") (class "Default")
      (node (ref "R6") (pin "2") (pinfunction "2_2") (pintype "passive"))
      (node (ref "U2") (pin "24") (pinfunction "VCC_24") (pintype "passive"))
    )
    (net (code "53") (name "Pack+") (class "Default")
      (node (ref "C12") (pin "1") (pinfunction "1_1") (pintype "passive"))
      (node (ref "C13") (pin "1") (pinfunction "1_1") (pintype "passive"))
      (node (ref "C2") (pin "1") (pinfunction "1_1") (pintype "passive"))
      (node (ref "D2") (pin "1") (pinfunction "1_1") (pintype "passive"))
      (node (ref "F3") (pin "2") (pinfunction "2_2") (pintype "passive"))
      (node (ref "J3") (pin "1") (pinfunction "1_1") (pintype "passive"))
      (node (ref "Q2") (pin "2") (pinfunction "2_2") (pintype "passive"))
      (node (ref "Q4") (pin "3") (pinfunction "3_3") (pintype "passive"))
      (node (ref "R14") (pin "1") (pinfunction "1_1") (pintype "passive"))
      (node (ref "R25") (pin "1") (pinfunction "1_1") (pintype "passive"))
      (node (ref "R29") (pin "1") (pinfunction "1_1") (pintype "passive"))
      (node (ref "R3") (pin "1") (pinfunction "1_1") (pintype "passive"))
      (node (ref "R8") (pin "1") (pinfunction "1_1") (pintype "passive"))
    )
    (net (code "54") (name "Pack-") (class "Default")
      (node (ref "C12") (pin "2") (pinfunction "2_2") (pintype "passive"))
      (node (ref "C13") (pin "2") (pinfunction "2_2") (pintype "passive"))
      (node (ref "C17") (pin "2") (pinfunction "2_2") (pintype "passive"))
      (node (ref "J1") (pin "2") (pinfunction "2_2") (pintype "passive"))
      (node (ref "J5") (pin "1") (pinfunction "1_1") (pintype "passive"))
      (node (ref "J7") (pin "2") (pinfunction "2_2") (pintype "passive"))
      (node (ref "J7") (pin "S1") (pinfunction "SHIELD1_S1") (pintype "passive"))
      (node (ref "J7") (pin "S2") (pinfunction "SHIELD2_S2") (pintype "passive"))
      (node (ref "J8") (pin "2") (pinfunction "2_2") (pintype "passive"))
      (node (ref "J8") (pin "S1") (pinfunction "SHIELD1_S1") (pintype "passive"))
      (node (ref "J8") (pin "S2") (pinfunction "SHIELD2_S2") (pintype "passive"))
      (node (ref "R18") (pin "2") (pinfunction "2_2") (pintype "passive"))
      (node (ref "R19") (pin "2") (pinfunction "2_2") (pintype "passive"))
      (node (ref "R20") (pin "2") (pinfunction "2_2") (pintype "passive"))
      (node (ref "U2") (pin "6") (pinfunction "SRN_6") (pintype "passive"))
    )
  )
)
